# BackBoard.net
KiCad netlist of a schematic drawn in Altium Designer
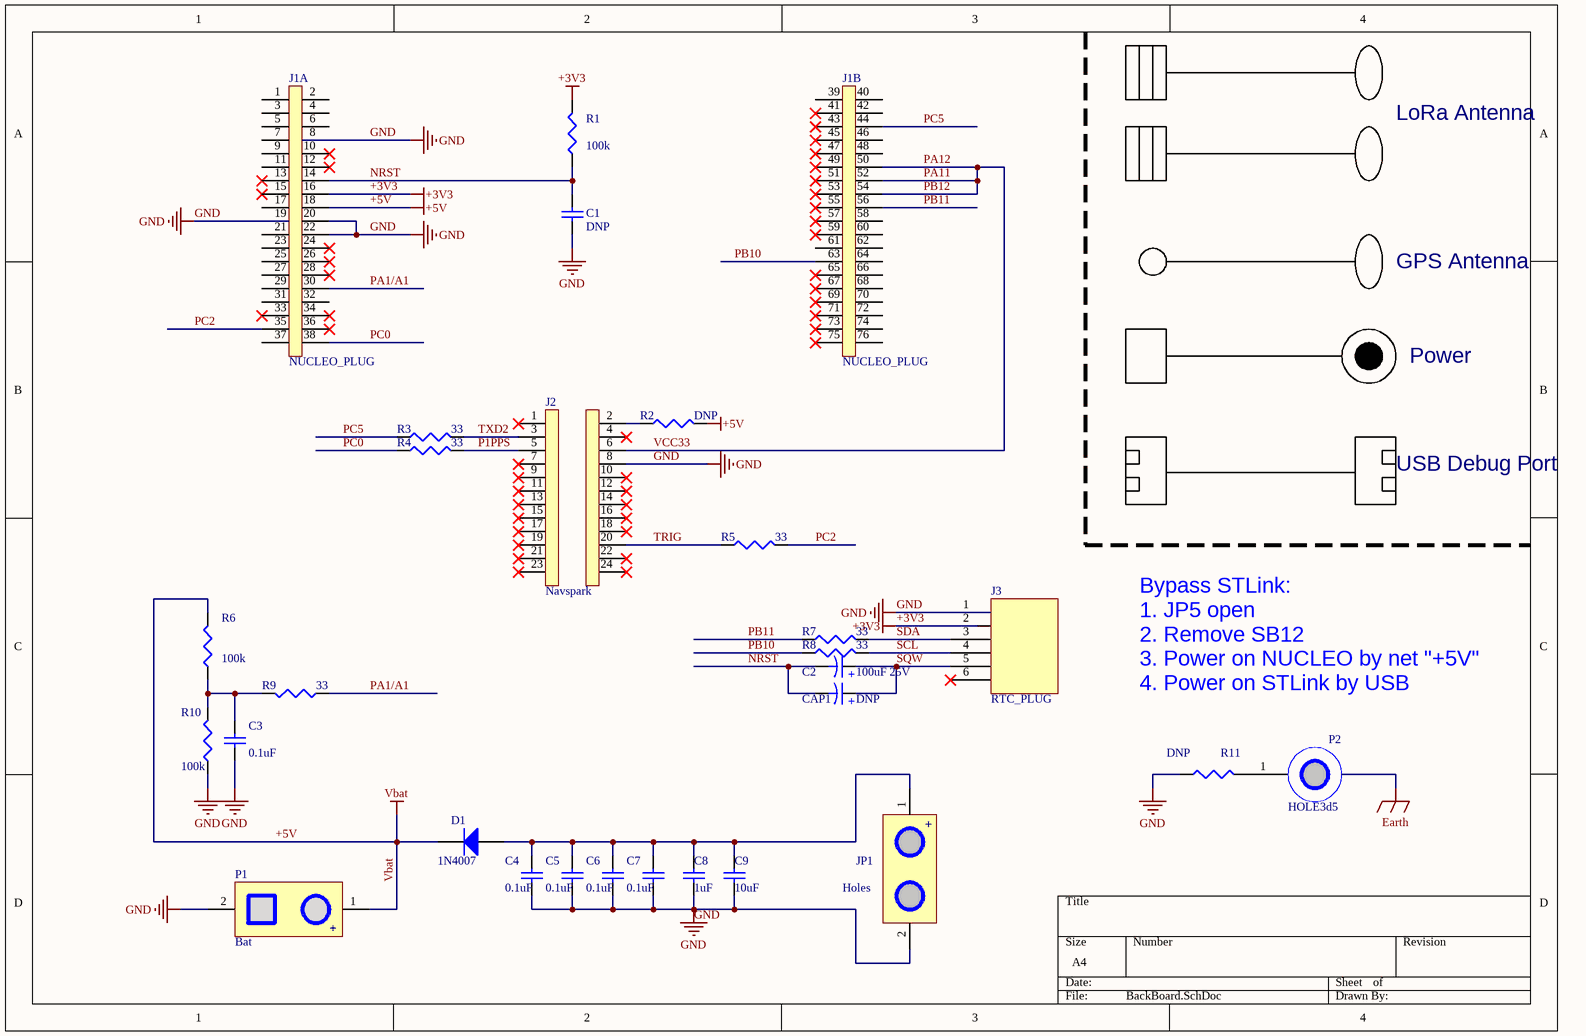
[diagram p0: BackBoard.SchDoc]

(export (version "E")
  (design (tool "Eeschema 10.0.6"))
  (components
    (comp (ref "C1")
      (value "DNP")
      (footprint "C0805")
      (description "Capacitor")
      (fields (field (name "PUBLISHER") "Altium Limited"))
      (libsource (lib "Schlib1") (part "Capacitor"))
    )
    (comp (ref "C2")
      (value "100uF 25V")
      (footprint "C7343")
      (description "Polarized Capacitor")
      (fields (field (name "Comment") "100u 25V") (field (name "PUBLISHER") "Altium Limited"))
      (libsource (lib "Schlib1") (part "100u 25V"))
    )
    (comp (ref "C3")
      (value "0.1u")
      (footprint "C0805")
      (description "Capacitor")
      (fields (field (name "0.1") "0.1uF") (field (name "PUBLISHER") "Altium Limited"))
      (libsource (lib "Schlib1") (part "0.1u"))
    )
    (comp (ref "C4")
      (value "0.1u")
      (footprint "C0805")
      (description "Capacitor")
      (fields (field (name "0.1") "0.1uF") (field (name "PUBLISHER") "Altium Limited"))
      (libsource (lib "Schlib1") (part "0.1u"))
    )
    (comp (ref "C5")
      (value "0.1u")
      (footprint "C0805")
      (description "Capacitor")
      (fields (field (name "0.1") "0.1uF") (field (name "PUBLISHER") "Altium Limited"))
      (libsource (lib "Schlib1") (part "0.1u"))
    )
    (comp (ref "C6")
      (value "0.1u")
      (footprint "C0805")
      (description "Capacitor")
      (fields (field (name "0.1") "0.1uF") (field (name "PUBLISHER") "Altium Limited"))
      (libsource (lib "Schlib1") (part "0.1u"))
    )
    (comp (ref "C7")
      (value "0.1u")
      (footprint "C0805")
      (description "Capacitor")
      (fields (field (name "0.1") "0.1uF") (field (name "PUBLISHER") "Altium Limited"))
      (libsource (lib "Schlib1") (part "0.1u"))
    )
    (comp (ref "C8")
      (value "1u")
      (footprint "C0805")
      (description "Capacitor")
      (fields (field (name "1") "1uF") (field (name "PUBLISHER") "Altium Limited"))
      (libsource (lib "Schlib1") (part "1u"))
    )
    (comp (ref "C9")
      (value "10u")
      (footprint "C1206")
      (description "Capacitor")
      (fields (field (name "1") "10uF") (field (name "PUBLISHER") "Altium Limited"))
      (libsource (lib "Schlib1") (part "10u"))
    )
    (comp (ref "CAP1")
      (value "DNP")
      (footprint "TESTBED_IN4007-20210118P4:CP2V_D10R0_5R0")
      (description "Polarized Capacitor")
      (fields (field (name "PUBLISHER") "Altium Limited"))
      (libsource (lib "Schlib1") (part "Aluminum electrolytic capacitor"))
    )
    (comp (ref "D1")
      (value "1N4007")
      (footprint "TESTBED_IN4007-20210118P4:2D7X2")
      (description "1 Amp General Purpose Rectifier")
      (fields (field (name "PUBLISHER") "Altium Limited"))
      (libsource (lib "Schlib1") (part "1N4007"))
    )
    (comp (ref "J1")
      (value "NUCLEO_PLUG")
      (footprint "38pX2")
      (description "NUCLEO")
      (libsource (lib "Schlib1") (part "NUCLEO_PLUG"))
    )
    (comp (ref "J2")
      (value "Navspark")
      (footprint "TESTBED_IN4007-20210118P4:12pX2_2d54_15d24")
      (libsource (lib "Schlib1") (part "Navspark"))
    )
    (comp (ref "J3")
      (value "RTC_PLUG")
      (footprint "TESTBED_IN4007-20210118P4:2D54_6P_FEMALE_SMT")
      (description "RTC")
      (libsource (lib "Schlib1") (part "RTC_PLUG"))
    )
    (comp (ref "JP1")
      (value "Holes")
      (footprint "TESTBED_IN4007-20210118P4:3D81X2")
      (description "Power")
      (libsource (lib "Schlib1") (part "Holes"))
    )
    (comp (ref "P1")
      (value "Bat")
      (footprint "TESTBED_IN4007-20210118P4:MY_2PIN")
      (libsource (lib "Schlib1") (part "Bat"))
    )
    (comp (ref "P2")
      (value "HOLE3d5")
      (footprint "TESTBED_IN4007-20210118P4:I3D5_O6MM")
      (description "Chassis earth")
      (libsource (lib "Schlib1") (part "HOLE3d5"))
    )
    (comp (ref "R1")
      (value "100k")
      (footprint "TESTBED_IN4007-20210118P4:R0805")
      (description "Resistor")
      (fields (field (name "PUBLISHER") "Altium Limited"))
      (libsource (lib "Schlib1") (part "100k"))
    )
    (comp (ref "R2")
      (value "DNP")
      (footprint "TESTBED_IN4007-20210118P4:R0805")
      (description "Resistor")
      (fields (field (name "PUBLISHER") "Altium Limited"))
      (libsource (lib "Schlib1") (part "Resistor"))
    )
    (comp (ref "R3")
      (value "33")
      (footprint "TESTBED_IN4007-20210118P4:R0805")
      (description "Resistor")
      (fields (field (name "PUBLISHER") "Altium Limited"))
      (libsource (lib "Schlib1") (part "33"))
    )
    (comp (ref "R4")
      (value "33")
      (footprint "TESTBED_IN4007-20210118P4:R0805")
      (description "Resistor")
      (fields (field (name "PUBLISHER") "Altium Limited"))
      (libsource (lib "Schlib1") (part "33"))
    )
    (comp (ref "R5")
      (value "33")
      (footprint "TESTBED_IN4007-20210118P4:R0805")
      (description "Resistor")
      (fields (field (name "PUBLISHER") "Altium Limited"))
      (libsource (lib "Schlib1") (part "33"))
    )
    (comp (ref "R6")
      (value "100k")
      (footprint "TESTBED_IN4007-20210118P4:R0805")
      (description "Resistor")
      (fields (field (name "PUBLISHER") "Altium Limited"))
      (libsource (lib "Schlib1") (part "100k"))
    )
    (comp (ref "R7")
      (value "33")
      (footprint "TESTBED_IN4007-20210118P4:R0805")
      (description "Resistor")
      (fields (field (name "PUBLISHER") "Altium Limited"))
      (libsource (lib "Schlib1") (part "33"))
    )
    (comp (ref "R8")
      (value "33")
      (footprint "TESTBED_IN4007-20210118P4:R0805")
      (description "Resistor")
      (fields (field (name "PUBLISHER") "Altium Limited"))
      (libsource (lib "Schlib1") (part "33"))
    )
    (comp (ref "R9")
      (value "33")
      (footprint "TESTBED_IN4007-20210118P4:R0805")
      (description "Resistor")
      (fields (field (name "PUBLISHER") "Altium Limited"))
      (libsource (lib "Schlib1") (part "33"))
    )
    (comp (ref "R10")
      (value "100k")
      (footprint "TESTBED_IN4007-20210118P4:R0805")
      (description "Resistor")
      (fields (field (name "PUBLISHER") "Altium Limited"))
      (libsource (lib "Schlib1") (part "100k"))
    )
    (comp (ref "R11")
      (value "DNP")
      (footprint "TESTBED_IN4007-20210118P4:R0805")
      (description "Resistor")
      (fields (field (name "PUBLISHER") "Altium Limited"))
      (libsource (lib "Schlib1") (part "Resistor"))
    )
  )
  (nets
    (net (code "1") (name "+3V3") (class "Default")
      (node (ref "R1") (pin "2") (pinfunction "2_2") (pintype "passive"))
    )
    (net (code "2") (name "+5V") (class "Default")
      (node (ref "D1") (pin "2") (pinfunction "K_2") (pintype "passive"))
      (node (ref "R2") (pin "2") (pinfunction "2_2") (pintype "passive"))
      (node (ref "R6") (pin "2") (pinfunction "2_2") (pintype "passive"))
    )
    (net (code "3") (name "/NRST") (class "Default")
      (node (ref "C1") (pin "2") (pinfunction "2_2") (pintype "passive"))
      (node (ref "C2") (pin "2") (pinfunction "2_2") (pintype "passive"))
      (node (ref "CAP1") (pin "2") (pinfunction "2_2") (pintype "passive"))
      (node (ref "R1") (pin "1") (pinfunction "1_1") (pintype "passive"))
    )
    (net (code "4") (name "/P1PPS") (class "Default")
      (node (ref "R4") (pin "2") (pinfunction "2_2") (pintype "passive"))
    )
    (net (code "5") (name "/PA1{slash}A1") (class "Default")
      (node (ref "R9") (pin "1") (pinfunction "1_1") (pintype "passive"))
    )
    (net (code "7") (name "/PB10") (class "Default")
      (node (ref "R8") (pin "1") (pinfunction "1_1") (pintype "passive"))
    )
    (net (code "8") (name "/PB11") (class "Default")
      (node (ref "R7") (pin "1") (pinfunction "1_1") (pintype "passive"))
    )
    (net (code "9") (name "/PC0") (class "Default")
      (node (ref "R4") (pin "1") (pinfunction "1_1") (pintype "passive"))
    )
    (net (code "10") (name "/PC2") (class "Default")
      (node (ref "R5") (pin "2") (pinfunction "2_2") (pintype "passive"))
    )
    (net (code "11") (name "/PC5") (class "Default")
      (node (ref "R3") (pin "1") (pinfunction "1_1") (pintype "passive"))
    )
    (net (code "12") (name "/SCL") (class "Default")
      (node (ref "R8") (pin "2") (pinfunction "2_2") (pintype "passive"))
    )
    (net (code "13") (name "/SDA") (class "Default")
      (node (ref "R7") (pin "2") (pinfunction "2_2") (pintype "passive"))
    )
    (net (code "14") (name "/SQW") (class "Default")
      (node (ref "C2") (pin "1") (pinfunction "1_1") (pintype "passive"))
      (node (ref "CAP1") (pin "1") (pinfunction "1_1") (pintype "passive"))
    )
    (net (code "15") (name "/TRIG") (class "Default")
      (node (ref "R5") (pin "1") (pinfunction "1_1") (pintype "passive"))
    )
    (net (code "16") (name "/TXD2") (class "Default")
      (node (ref "R3") (pin "2") (pinfunction "2_2") (pintype "passive"))
    )
    (net (code "18") (name "GND") (class "Default")
      (node (ref "C1") (pin "1") (pinfunction "1_1") (pintype "passive"))
      (node (ref "C3") (pin "1") (pinfunction "1_1") (pintype "passive"))
      (node (ref "C4") (pin "1") (pinfunction "1_1") (pintype "passive"))
      (node (ref "C5") (pin "1") (pinfunction "1_1") (pintype "passive"))
      (node (ref "C6") (pin "1") (pinfunction "1_1") (pintype "passive"))
      (node (ref "C7") (pin "1") (pinfunction "1_1") (pintype "passive"))
      (node (ref "C8") (pin "1") (pinfunction "1_1") (pintype "passive"))
      (node (ref "C9") (pin "1") (pinfunction "1_1") (pintype "passive"))
      (node (ref "J1") (pin "19") (pinfunction "19_19") (pintype "passive"))
      (node (ref "J1") (pin "8") (pinfunction "8_8") (pintype "passive"))
      (node (ref "J3") (pin "1") (pinfunction "1_1") (pintype "passive"))
      (node (ref "R10") (pin "1") (pinfunction "1_1") (pintype "passive"))
      (node (ref "R11") (pin "1") (pinfunction "1_1") (pintype "passive"))
    )
    (net (code "19") (name "Net-(C3-Pad2)") (class "Default")
      (node (ref "C3") (pin "2") (pinfunction "2_2") (pintype "passive"))
      (node (ref "R10") (pin "2") (pinfunction "2_2") (pintype "passive"))
      (node (ref "R6") (pin "1") (pinfunction "1_1") (pintype "passive"))
      (node (ref "R9") (pin "2") (pinfunction "2_2") (pintype "passive"))
    )
    (net (code "20") (name "Net-(D1-A)") (class "Default")
      (node (ref "C4") (pin "2") (pinfunction "2_2") (pintype "passive"))
      (node (ref "C5") (pin "2") (pinfunction "2_2") (pintype "passive"))
      (node (ref "C6") (pin "2") (pinfunction "2_2") (pintype "passive"))
      (node (ref "C7") (pin "2") (pinfunction "2_2") (pintype "passive"))
      (node (ref "C8") (pin "2") (pinfunction "2_2") (pintype "passive"))
      (node (ref "C9") (pin "2") (pinfunction "2_2") (pintype "passive"))
      (node (ref "D1") (pin "1") (pinfunction "A_1") (pintype "passive"))
    )
    (net (code "21") (name "unconnected-(J1-Pad1)") (class "Default")
      (node (ref "J1") (pin "1") (pinfunction "1_1") (pintype "passive"))
    )
    (net (code "22") (name "unconnected-(J1-Pad2)") (class "Default")
      (node (ref "J1") (pin "2") (pinfunction "2_2") (pintype "passive"))
    )
    (net (code "23") (name "unconnected-(J1-Pad3)") (class "Default")
      (node (ref "J1") (pin "3") (pinfunction "3_3") (pintype "passive"))
    )
    (net (code "24") (name "unconnected-(J1-Pad4)") (class "Default")
      (node (ref "J1") (pin "4") (pinfunction "4_4") (pintype "passive"))
    )
    (net (code "25") (name "unconnected-(J1-Pad5)") (class "Default")
      (node (ref "J1") (pin "5") (pinfunction "5_5") (pintype "passive"))
    )
    (net (code "26") (name "unconnected-(J1-Pad6)") (class "Default")
      (node (ref "J1") (pin "6") (pinfunction "6_6") (pintype "passive"))
    )
    (net (code "27") (name "unconnected-(J1-Pad7)") (class "Default")
      (node (ref "J1") (pin "7") (pinfunction "7_7") (pintype "passive"))
    )
    (net (code "28") (name "unconnected-(J1-Pad9)") (class "Default")
      (node (ref "J1") (pin "9") (pinfunction "9_9") (pintype "passive"))
    )
    (net (code "29") (name "unconnected-(J1-Pad10)") (class "Default")
      (node (ref "J1") (pin "10") (pinfunction "10_10") (pintype "passive"))
    )
    (net (code "30") (name "unconnected-(J1-Pad11)") (class "Default")
      (node (ref "J1") (pin "11") (pinfunction "11_11") (pintype "passive"))
    )
    (net (code "31") (name "unconnected-(J1-Pad12)") (class "Default")
      (node (ref "J1") (pin "12") (pinfunction "12_12") (pintype "passive"))
    )
    (net (code "32") (name "unconnected-(J1-Pad13)") (class "Default")
      (node (ref "J1") (pin "13") (pinfunction "13_13") (pintype "passive"))
    )
    (net (code "33") (name "unconnected-(J1-Pad14)") (class "Default")
      (node (ref "J1") (pin "14") (pinfunction "14_14") (pintype "passive"))
    )
    (net (code "34") (name "unconnected-(J1-Pad15)") (class "Default")
      (node (ref "J1") (pin "15") (pinfunction "15_15") (pintype "passive"))
    )
    (net (code "35") (name "unconnected-(J1-Pad16)") (class "Default")
      (node (ref "J1") (pin "16") (pinfunction "16_16") (pintype "passive"))
    )
    (net (code "36") (name "unconnected-(J1-Pad17)") (class "Default")
      (node (ref "J1") (pin "17") (pinfunction "17_17") (pintype "passive"))
    )
    (net (code "37") (name "unconnected-(J1-Pad18)") (class "Default")
      (node (ref "J1") (pin "18") (pinfunction "18_18") (pintype "passive"))
    )
    (net (code "38") (name "unconnected-(J1-Pad20)") (class "Default")
      (node (ref "J1") (pin "20") (pinfunction "20_20") (pintype "passive"))
    )
    (net (code "39") (name "unconnected-(J1-Pad21)") (class "Default")
      (node (ref "J1") (pin "21") (pinfunction "21_21") (pintype "passive"))
    )
    (net (code "40") (name "unconnected-(J1-Pad22)") (class "Default")
      (node (ref "J1") (pin "22") (pinfunction "22_22") (pintype "passive"))
    )
    (net (code "41") (name "unconnected-(J1-Pad23)") (class "Default")
      (node (ref "J1") (pin "23") (pinfunction "23_23") (pintype "passive"))
    )
    (net (code "42") (name "unconnected-(J1-Pad24)") (class "Default")
      (node (ref "J1") (pin "24") (pinfunction "24_24") (pintype "passive"))
    )
    (net (code "43") (name "unconnected-(J1-Pad25)") (class "Default")
      (node (ref "J1") (pin "25") (pinfunction "25_25") (pintype "passive"))
    )
    (net (code "44") (name "unconnected-(J1-Pad26)") (class "Default")
      (node (ref "J1") (pin "26") (pinfunction "26_26") (pintype "passive"))
    )
    (net (code "45") (name "unconnected-(J1-Pad27)") (class "Default")
      (node (ref "J1") (pin "27") (pinfunction "27_27") (pintype "passive"))
    )
    (net (code "46") (name "unconnected-(J1-Pad28)") (class "Default")
      (node (ref "J1") (pin "28") (pinfunction "28_28") (pintype "passive"))
    )
    (net (code "47") (name "unconnected-(J1-Pad29)") (class "Default")
      (node (ref "J1") (pin "29") (pinfunction "29_29") (pintype "passive"))
    )
    (net (code "48") (name "unconnected-(J1-Pad30)") (class "Default")
      (node (ref "J1") (pin "30") (pinfunction "30_30") (pintype "passive"))
    )
    (net (code "49") (name "unconnected-(J1-Pad31)") (class "Default")
      (node (ref "J1") (pin "31") (pinfunction "31_31") (pintype "passive"))
    )
    (net (code "50") (name "unconnected-(J1-Pad32)") (class "Default")
      (node (ref "J1") (pin "32") (pinfunction "32_32") (pintype "passive"))
    )
    (net (code "51") (name "unconnected-(J1-Pad33)") (class "Default")
      (node (ref "J1") (pin "33") (pinfunction "33_33") (pintype "passive"))
    )
    (net (code "52") (name "unconnected-(J1-Pad34)") (class "Default")
      (node (ref "J1") (pin "34") (pinfunction "34_34") (pintype "passive"))
    )
    (net (code "53") (name "unconnected-(J1-Pad35)") (class "Default")
      (node (ref "J1") (pin "35") (pinfunction "35_35") (pintype "passive"))
    )
    (net (code "54") (name "unconnected-(J1-Pad36)") (class "Default")
      (node (ref "J1") (pin "36") (pinfunction "36_36") (pintype "passive"))
    )
    (net (code "55") (name "unconnected-(J1-Pad37)") (class "Default")
      (node (ref "J1") (pin "37") (pinfunction "37_37") (pintype "passive"))
    )
    (net (code "56") (name "unconnected-(J1-Pad38)") (class "Default")
      (node (ref "J1") (pin "38") (pinfunction "38_38") (pintype "passive"))
    )
    (net (code "57") (name "unconnected-(J1-Pad39)") (class "Default")
      (node (ref "J1") (pin "39") (pinfunction "39_39") (pintype "passive"))
    )
    (net (code "58") (name "unconnected-(J1-Pad40)") (class "Default")
      (node (ref "J1") (pin "40") (pinfunction "40_40") (pintype "passive"))
    )
    (net (code "59") (name "unconnected-(J1-Pad41)") (class "Default")
      (node (ref "J1") (pin "41") (pinfunction "41_41") (pintype "passive"))
    )
    (net (code "60") (name "unconnected-(J1-Pad42)") (class "Default")
      (node (ref "J1") (pin "42") (pinfunction "42_42") (pintype "passive"))
    )
    (net (code "61") (name "unconnected-(J1-Pad43)") (class "Default")
      (node (ref "J1") (pin "43") (pinfunction "43_43") (pintype "passive"))
    )
    (net (code "62") (name "unconnected-(J1-Pad44)") (class "Default")
      (node (ref "J1") (pin "44") (pinfunction "44_44") (pintype "passive"))
    )
    (net (code "63") (name "unconnected-(J1-Pad45)") (class "Default")
      (node (ref "J1") (pin "45") (pinfunction "45_45") (pintype "passive"))
    )
    (net (code "64") (name "unconnected-(J1-Pad46)") (class "Default")
      (node (ref "J1") (pin "46") (pinfunction "46_46") (pintype "passive"))
    )
    (net (code "65") (name "unconnected-(J1-Pad47)") (class "Default")
      (node (ref "J1") (pin "47") (pinfunction "47_47") (pintype "passive"))
    )
    (net (code "66") (name "unconnected-(J1-Pad48)") (class "Default")
      (node (ref "J1") (pin "48") (pinfunction "48_48") (pintype "passive"))
    )
    (net (code "67") (name "unconnected-(J1-Pad49)") (class "Default")
      (node (ref "J1") (pin "49") (pinfunction "49_49") (pintype "passive"))
    )
    (net (code "68") (name "unconnected-(J1-Pad50)") (class "Default")
      (node (ref "J1") (pin "50") (pinfunction "50_50") (pintype "passive"))
    )
    (net (code "69") (name "unconnected-(J1-Pad51)") (class "Default")
      (node (ref "J1") (pin "51") (pinfunction "51_51") (pintype "passive"))
    )
    (net (code "70") (name "unconnected-(J1-Pad52)") (class "Default")
      (node (ref "J1") (pin "52") (pinfunction "52_52") (pintype "passive"))
    )
    (net (code "71") (name "unconnected-(J1-Pad53)") (class "Default")
      (node (ref "J1") (pin "53") (pinfunction "53_53") (pintype "passive"))
    )
    (net (code "72") (name "unconnected-(J1-Pad54)") (class "Default")
      (node (ref "J1") (pin "54") (pinfunction "54_54") (pintype "passive"))
    )
    (net (code "73") (name "unconnected-(J1-Pad55)") (class "Default")
      (node (ref "J1") (pin "55") (pinfunction "55_55") (pintype "passive"))
    )
    (net (code "74") (name "unconnected-(J1-Pad56)") (class "Default")
      (node (ref "J1") (pin "56") (pinfunction "56_56") (pintype "passive"))
    )
    (net (code "75") (name "unconnected-(J1-Pad57)") (class "Default")
      (node (ref "J1") (pin "57") (pinfunction "57_57") (pintype "passive"))
    )
    (net (code "76") (name "unconnected-(J1-Pad58)") (class "Default")
      (node (ref "J1") (pin "58") (pinfunction "58_58") (pintype "passive"))
    )
    (net (code "77") (name "unconnected-(J1-Pad59)") (class "Default")
      (node (ref "J1") (pin "59") (pinfunction "59_59") (pintype "passive"))
    )
    (net (code "78") (name "unconnected-(J1-Pad60)") (class "Default")
      (node (ref "J1") (pin "60") (pinfunction "60_60") (pintype "passive"))
    )
    (net (code "79") (name "unconnected-(J1-Pad61)") (class "Default")
      (node (ref "J1") (pin "61") (pinfunction "61_61") (pintype "passive"))
    )
    (net (code "80") (name "unconnected-(J1-Pad62)") (class "Default")
      (node (ref "J1") (pin "62") (pinfunction "62_62") (pintype "passive"))
    )
    (net (code "81") (name "unconnected-(J1-Pad63)") (class "Default")
      (node (ref "J1") (pin "63") (pinfunction "63_63") (pintype "passive"))
    )
    (net (code "82") (name "unconnected-(J1-Pad64)") (class "Default")
      (node (ref "J1") (pin "64") (pinfunction "64_64") (pintype "passive"))
    )
    (net (code "83") (name "unconnected-(J1-Pad65)") (class "Default")
      (node (ref "J1") (pin "65") (pinfunction "65_65") (pintype "passive"))
    )
    (net (code "84") (name "unconnected-(J1-Pad66)") (class "Default")
      (node (ref "J1") (pin "66") (pinfunction "66_66") (pintype "passive"))
    )
    (net (code "85") (name "unconnected-(J1-Pad67)") (class "Default")
      (node (ref "J1") (pin "67") (pinfunction "67_67") (pintype "passive"))
    )
    (net (code "86") (name "unconnected-(J1-Pad68)") (class "Default")
      (node (ref "J1") (pin "68") (pinfunction "68_68") (pintype "passive"))
    )
    (net (code "87") (name "unconnected-(J1-Pad69)") (class "Default")
      (node (ref "J1") (pin "69") (pinfunction "69_69") (pintype "passive"))
    )
    (net (code "88") (name "unconnected-(J1-Pad70)") (class "Default")
      (node (ref "J1") (pin "70") (pinfunction "70_70") (pintype "passive"))
    )
    (net (code "89") (name "unconnected-(J1-Pad71)") (class "Default")
      (node (ref "J1") (pin "71") (pinfunction "71_71") (pintype "passive"))
    )
    (net (code "90") (name "unconnected-(J1-Pad72)") (class "Default")
      (node (ref "J1") (pin "72") (pinfunction "72_72") (pintype "passive"))
    )
    (net (code "91") (name "unconnected-(J1-Pad73)") (class "Default")
      (node (ref "J1") (pin "73") (pinfunction "73_73") (pintype "passive"))
    )
    (net (code "92") (name "unconnected-(J1-Pad74)") (class "Default")
      (node (ref "J1") (pin "74") (pinfunction "74_74") (pintype "passive"))
    )
    (net (code "93") (name "unconnected-(J1-Pad75)") (class "Default")
      (node (ref "J1") (pin "75") (pinfunction "75_75") (pintype "passive"))
    )
    (net (code "94") (name "unconnected-(J1-Pad76)") (class "Default")
      (node (ref "J1") (pin "76") (pinfunction "76_76") (pintype "passive"))
    )
    (net (code "95") (name "unconnected-(J2-Pad1)") (class "Default")
      (node (ref "J2") (pin "1") (pinfunction "1_1") (pintype "passive"))
    )
    (net (code "96") (name "unconnected-(J2-Pad2)") (class "Default")
      (node (ref "J2") (pin "2") (pinfunction "2_2") (pintype "passive"))
    )
    (net (code "97") (name "unconnected-(J2-Pad3)") (class "Default")
      (node (ref "J2") (pin "3") (pinfunction "3_3") (pintype "passive"))
    )
    (net (code "98") (name "unconnected-(J2-Pad4)") (class "Default")
      (node (ref "J2") (pin "4") (pinfunction "4_4") (pintype "passive"))
    )
    (net (code "99") (name "unconnected-(J2-Pad5)") (class "Default")
      (node (ref "J2") (pin "5") (pinfunction "5_5") (pintype "passive"))
    )
    (net (code "100") (name "unconnected-(J2-Pad6)") (class "Default")
      (node (ref "J2") (pin "6") (pinfunction "6_6") (pintype "passive"))
    )
    (net (code "101") (name "unconnected-(J2-Pad7)") (class "Default")
      (node (ref "J2") (pin "7") (pinfunction "7_7") (pintype "passive"))
    )
    (net (code "102") (name "unconnected-(J2-Pad8)") (class "Default")
      (node (ref "J2") (pin "8") (pinfunction "8_8") (pintype "passive"))
    )
    (net (code "103") (name "unconnected-(J2-Pad9)") (class "Default")
      (node (ref "J2") (pin "9") (pinfunction "9_9") (pintype "passive"))
    )
    (net (code "104") (name "unconnected-(J2-Pad10)") (class "Default")
      (node (ref "J2") (pin "10") (pinfunction "10_10") (pintype "passive"))
    )
    (net (code "105") (name "unconnected-(J2-Pad11)") (class "Default")
      (node (ref "J2") (pin "11") (pinfunction "11_11") (pintype "passive"))
    )
    (net (code "106") (name "unconnected-(J2-Pad12)") (class "Default")
      (node (ref "J2") (pin "12") (pinfunction "12_12") (pintype "passive"))
    )
    (net (code "107") (name "unconnected-(J2-Pad13)") (class "Default")
      (node (ref "J2") (pin "13") (pinfunction "13_13") (pintype "passive"))
    )
    (net (code "108") (name "unconnected-(J2-Pad14)") (class "Default")
      (node (ref "J2") (pin "14") (pinfunction "14_14") (pintype "passive"))
    )
    (net (code "109") (name "unconnected-(J2-Pad15)") (class "Default")
      (node (ref "J2") (pin "15") (pinfunction "15_15") (pintype "passive"))
    )
    (net (code "110") (name "unconnected-(J2-Pad16)") (class "Default")
      (node (ref "J2") (pin "16") (pinfunction "16_16") (pintype "passive"))
    )
    (net (code "111") (name "unconnected-(J2-Pad17)") (class "Default")
      (node (ref "J2") (pin "17") (pinfunction "17_17") (pintype "passive"))
    )
    (net (code "112") (name "unconnected-(J2-Pad18)") (class "Default")
      (node (ref "J2") (pin "18") (pinfunction "18_18") (pintype "passive"))
    )
    (net (code "113") (name "unconnected-(J2-Pad19)") (class "Default")
      (node (ref "J2") (pin "19") (pinfunction "19_19") (pintype "passive"))
    )
    (net (code "114") (name "unconnected-(J2-Pad20)") (class "Default")
      (node (ref "J2") (pin "20") (pinfunction "20_20") (pintype "passive"))
    )
    (net (code "115") (name "unconnected-(J2-Pad21)") (class "Default")
      (node (ref "J2") (pin "21") (pinfunction "21_21") (pintype "passive"))
    )
    (net (code "116") (name "unconnected-(J2-Pad22)") (class "Default")
      (node (ref "J2") (pin "22") (pinfunction "22_22") (pintype "passive"))
    )
    (net (code "117") (name "unconnected-(J2-Pad23)") (class "Default")
      (node (ref "J2") (pin "23") (pinfunction "23_23") (pintype "passive"))
    )
    (net (code "118") (name "unconnected-(J2-Pad24)") (class "Default")
      (node (ref "J2") (pin "24") (pinfunction "24_24") (pintype "passive"))
    )
    (net (code "119") (name "unconnected-(J3-3-Pad2)") (class "Default")
      (node (ref "J3") (pin "2") (pinfunction "3_2") (pintype "passive"))
    )
    (net (code "120") (name "unconnected-(J3-Pad3)") (class "Default")
      (node (ref "J3") (pin "3") (pinfunction "3_3") (pintype "passive"))
    )
    (net (code "121") (name "unconnected-(J3-Pad4)") (class "Default")
      (node (ref "J3") (pin "4") (pinfunction "4_4") (pintype "passive"))
    )
    (net (code "122") (name "unconnected-(J3-Pad5)") (class "Default")
      (node (ref "J3") (pin "5") (pinfunction "5_5") (pintype "passive"))
    )
    (net (code "123") (name "unconnected-(J3-Pad6)") (class "Default")
      (node (ref "J3") (pin "6") (pinfunction "6_6") (pintype "passive"))
    )
    (net (code "124") (name "unconnected-(JP1-Pad1)") (class "Default")
      (node (ref "JP1") (pin "1") (pinfunction "1_1") (pintype "passive"))
    )
    (net (code "125") (name "unconnected-(JP1-Pad2)") (class "Default")
      (node (ref "JP1") (pin "2") (pinfunction "2_2") (pintype "passive"))
    )
    (net (code "126") (name "unconnected-(P1-Pad1)") (class "Default")
      (node (ref "P1") (pin "1") (pinfunction "1_1") (pintype "passive"))
    )
    (net (code "127") (name "unconnected-(P1-Pad2)") (class "Default")
      (node (ref "P1") (pin "2") (pinfunction "2_2") (pintype "passive"))
    )
    (net (code "128") (name "unconnected-(P2-Pad1)") (class "Default")
      (node (ref "P2") (pin "1") (pinfunction "1_1") (pintype "passive"))
    )
    (net (code "129") (name "unconnected-(R2-Pad1)") (class "Default")
      (node (ref "R2") (pin "1") (pinfunction "1_1") (pintype "passive"))
    )
    (net (code "130") (name "unconnected-(R11-Pad2)") (class "Default")
      (node (ref "R11") (pin "2") (pinfunction "2_2") (pintype "passive"))
    )
  )
)
